# BioHackBoardPolulu.net
KiCad netlist of a schematic drawn in EAGLE
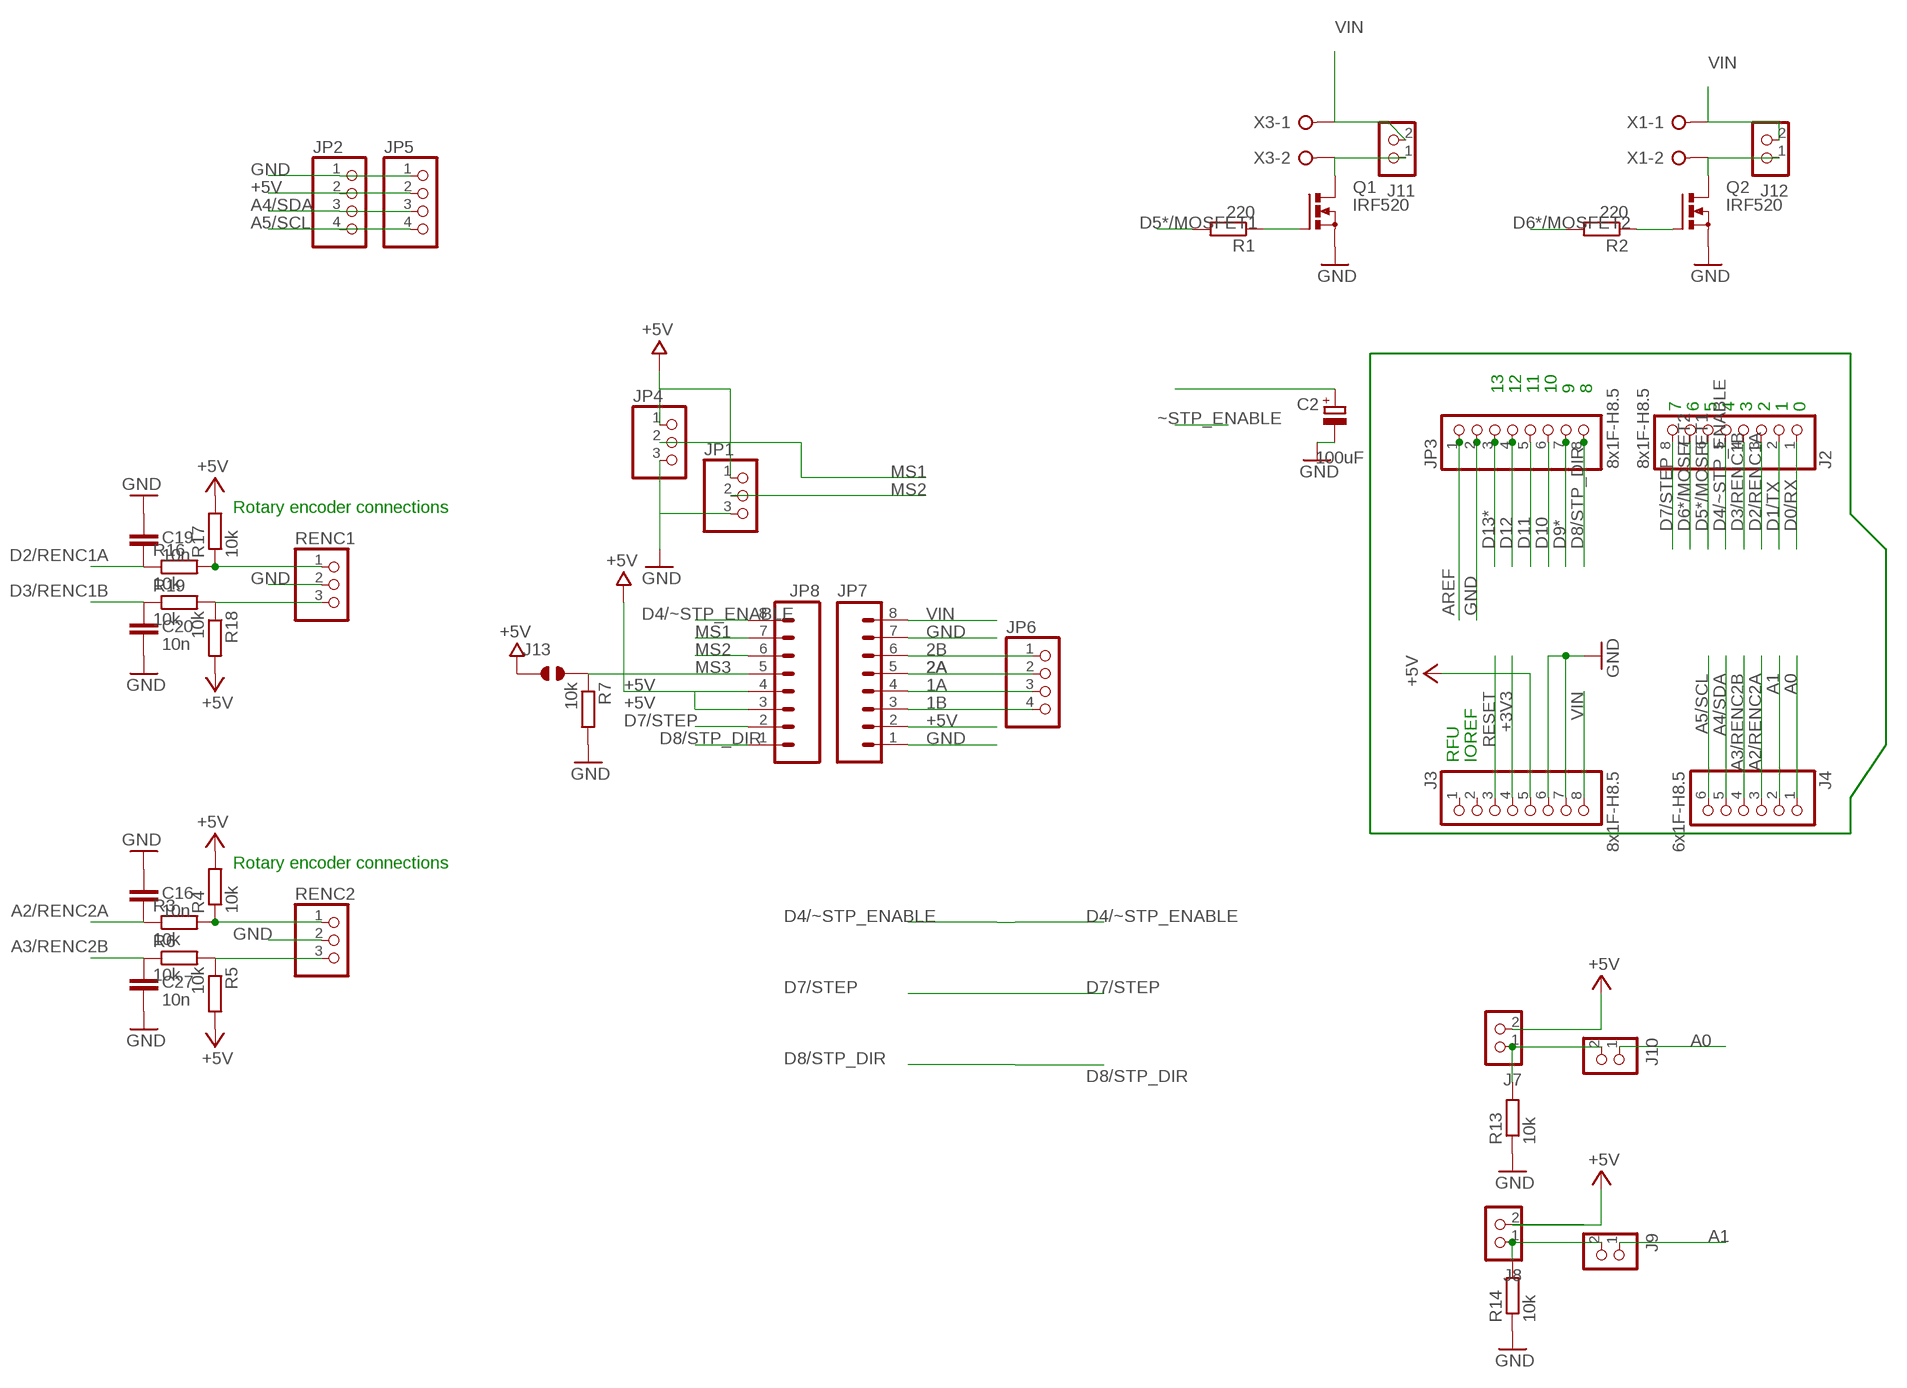
[diagram p0: schematic, sheet 1]

(export (version "E")
  (design (tool "Eeschema 10.0.6"))
  (components
    (comp (ref "C2")
      (value "100uF")
      (footprint "eagle-import:E2,5-7")
      (libsource (lib "eagle-import") (part "CPOL-EUE2.5-7"))
    )
    (comp (ref "C16")
      (value "10n")
      (footprint "eagle-import:C0603-ROUND")
      (libsource (lib "eagle-import") (part "C-EUC0603"))
    )
    (comp (ref "C19")
      (value "10n")
      (footprint "eagle-import:C0603-ROUND")
      (libsource (lib "eagle-import") (part "C-EUC0603"))
    )
    (comp (ref "C20")
      (value "10n")
      (footprint "eagle-import:C0603-ROUND")
      (libsource (lib "eagle-import") (part "C-EUC0603"))
    )
    (comp (ref "C27")
      (value "10n")
      (footprint "eagle-import:C0603-ROUND")
      (libsource (lib "eagle-import") (part "C-EUC0603"))
    )
    (comp (ref "J2")
      (value "8x1F-H8.5")
      (footprint "eagle-import:1X08-S")
      (libsource (lib "eagle-import") (part "PINHD-1X08_2.54-S"))
    )
    (comp (ref "J3")
      (value "8x1F-H8.5")
      (footprint "eagle-import:1X08-S")
      (libsource (lib "eagle-import") (part "PINHD-1X08_2.54-S"))
    )
    (comp (ref "J4")
      (value "6x1F-H8.5")
      (footprint "eagle-import:1X06-S")
      (libsource (lib "eagle-import") (part "PINHD-1X06_2.54-S"))
    )
    (comp (ref "J7")
      (value "CON_HEADER_1X02-PTH")
      (footprint "eagle-import:M1X2")
      (libsource (lib "eagle-import") (part "CON_HEADER_1X02-PTH"))
    )
    (comp (ref "J8")
      (value "CON_HEADER_1X02-PTH")
      (footprint "eagle-import:M1X2")
      (libsource (lib "eagle-import") (part "CON_HEADER_1X02-PTH"))
    )
    (comp (ref "J9")
      (value "CON_HEADER_1X02-PTH")
      (footprint "eagle-import:M1X2")
      (libsource (lib "eagle-import") (part "CON_HEADER_1X02-PTH"))
    )
    (comp (ref "J10")
      (value "CON_HEADER_1X02-PTH")
      (footprint "eagle-import:M1X2")
      (libsource (lib "eagle-import") (part "CON_HEADER_1X02-PTH"))
    )
    (comp (ref "J11")
      (value "CON_HEADER_1X02-PTH")
      (footprint "eagle-import:M1X2")
      (libsource (lib "eagle-import") (part "CON_HEADER_1X02-PTH"))
    )
    (comp (ref "J12")
      (value "CON_HEADER_1X02-PTH")
      (footprint "eagle-import:M1X2")
      (libsource (lib "eagle-import") (part "CON_HEADER_1X02-PTH"))
    )
    (comp (ref "J13")
      (value "JUMPER_SOLDER_1X2")
      (footprint "eagle-import:JUMPER_SOLDER_1X2")
      (libsource (lib "eagle-import") (part "JUMPER_SOLDER_1X2"))
    )
    (comp (ref "JP1")
      (value "PINHD-1X03_2.54-S")
      (footprint "eagle-import:1X03-S")
      (libsource (lib "eagle-import") (part "PINHD-1X03_2.54-S"))
    )
    (comp (ref "JP2")
      (value "PINHD-1X04_2.54-S")
      (footprint "eagle-import:1X04-S")
      (libsource (lib "eagle-import") (part "PINHD-1X04_2.54-S"))
    )
    (comp (ref "JP3")
      (value "8x1F-H8.5")
      (footprint "eagle-import:1X08-S")
      (libsource (lib "eagle-import") (part "PINHD-1X08_2.54-S"))
    )
    (comp (ref "JP4")
      (value "PINHD-1X03_2.54-S")
      (footprint "eagle-import:1X03-S")
      (libsource (lib "eagle-import") (part "PINHD-1X03_2.54-S"))
    )
    (comp (ref "JP5")
      (value "PINHD-1X04_2.54-S")
      (footprint "eagle-import:1X04-S")
      (libsource (lib "eagle-import") (part "PINHD-1X04_2.54-S"))
    )
    (comp (ref "JP6")
      (value "PINHD-1X04_2.54-S")
      (footprint "eagle-import:1X04-S")
      (libsource (lib "eagle-import") (part "PINHD-1X04_2.54-S"))
    )
    (comp (ref "JP7")
      (value "M081X08")
      (footprint "eagle-import:1X08")
      (libsource (lib "eagle-import") (part "M081X08"))
    )
    (comp (ref "JP8")
      (value "M081X08")
      (footprint "eagle-import:1X08")
      (libsource (lib "eagle-import") (part "M081X08"))
    )
    (comp (ref "Q1")
      (value "IRF520")
      (footprint "eagle-import:TO220BV")
      (libsource (lib "eagle-import") (part "IRF512"))
    )
    (comp (ref "Q2")
      (value "IRF520")
      (footprint "eagle-import:TO220BV")
      (libsource (lib "eagle-import") (part "IRF512"))
    )
    (comp (ref "R1")
      (value "220")
      (footprint "eagle-import:R0603-ROUND")
      (libsource (lib "eagle-import") (part "R-EU_R0603"))
    )
    (comp (ref "R2")
      (value "220")
      (footprint "eagle-import:R0603-ROUND")
      (libsource (lib "eagle-import") (part "R-EU_R0603"))
    )
    (comp (ref "R3")
      (value "10k")
      (footprint "eagle-import:R0603-ROUND")
      (libsource (lib "eagle-import") (part "R-EU_R0603"))
    )
    (comp (ref "R4")
      (value "10k")
      (footprint "eagle-import:R0603-ROUND")
      (libsource (lib "eagle-import") (part "R-EU_R0603"))
    )
    (comp (ref "R5")
      (value "10k")
      (footprint "eagle-import:R0603-ROUND")
      (libsource (lib "eagle-import") (part "R-EU_R0603"))
    )
    (comp (ref "R6")
      (value "10k")
      (footprint "eagle-import:R0603-ROUND")
      (libsource (lib "eagle-import") (part "R-EU_R0603"))
    )
    (comp (ref "R7")
      (value "10k")
      (footprint "eagle-import:R0603-ROUND")
      (libsource (lib "eagle-import") (part "R-EU_R0603"))
    )
    (comp (ref "R13")
      (value "10k")
      (footprint "eagle-import:R0603")
      (libsource (lib "eagle-import") (part "rcl_R-EU_R0603"))
    )
    (comp (ref "R14")
      (value "10k")
      (footprint "eagle-import:R0603")
      (libsource (lib "eagle-import") (part "rcl_R-EU_R0603"))
    )
    (comp (ref "R16")
      (value "10k")
      (footprint "eagle-import:R0603-ROUND")
      (libsource (lib "eagle-import") (part "R-EU_R0603"))
    )
    (comp (ref "R17")
      (value "10k")
      (footprint "eagle-import:R0603-ROUND")
      (libsource (lib "eagle-import") (part "R-EU_R0603"))
    )
    (comp (ref "R18")
      (value "10k")
      (footprint "eagle-import:R0603-ROUND")
      (libsource (lib "eagle-import") (part "R-EU_R0603"))
    )
    (comp (ref "R19")
      (value "10k")
      (footprint "eagle-import:R0603-ROUND")
      (libsource (lib "eagle-import") (part "R-EU_R0603"))
    )
    (comp (ref "RENC1")
      (value "PINHD-1X03_2.54-S")
      (footprint "eagle-import:1X03-S")
      (libsource (lib "eagle-import") (part "PINHD-1X03_2.54-S"))
    )
    (comp (ref "RENC2")
      (value "PINHD-1X03_2.54-S")
      (footprint "eagle-import:1X03-S")
      (libsource (lib "eagle-import") (part "PINHD-1X03_2.54-S"))
    )
    (comp (ref "X1")
      (value "W237-02P")
      (footprint "eagle-import:W237-132")
      (libsource (lib "eagle-import") (part "W237-02P"))
    )
    (comp (ref "X3")
      (value "W237-02P")
      (footprint "eagle-import:W237-132")
      (libsource (lib "eagle-import") (part "W237-02P"))
    )
  )
  (nets
    (net (code "1") (name "+5V") (class "Default")
      (node (ref "J13") (pin "1") (pinfunction "1_1") (pintype "passive"))
      (node (ref "J3") (pin "5") (pinfunction "5_5") (pintype "passive"))
      (node (ref "J7") (pin "2") (pinfunction "2_2") (pintype "passive"))
      (node (ref "J8") (pin "2") (pinfunction "2_2") (pintype "passive"))
      (node (ref "JP1") (pin "1") (pinfunction "1_1") (pintype "passive"))
      (node (ref "JP2") (pin "2") (pinfunction "2_2") (pintype "passive"))
      (node (ref "JP4") (pin "1") (pinfunction "1_1") (pintype "passive"))
      (node (ref "JP5") (pin "2") (pinfunction "2_2") (pintype "passive"))
      (node (ref "JP7") (pin "2") (pinfunction "2_2") (pintype "passive"))
      (node (ref "JP8") (pin "3") (pinfunction "3_3") (pintype "passive"))
      (node (ref "JP8") (pin "4") (pinfunction "4_4") (pintype "passive"))
      (node (ref "R17") (pin "2") (pinfunction "2_2") (pintype "passive"))
      (node (ref "R18") (pin "2") (pinfunction "2_2") (pintype "passive"))
      (node (ref "R4") (pin "2") (pinfunction "2_2") (pintype "passive"))
      (node (ref "R5") (pin "2") (pinfunction "2_2") (pintype "passive"))
    )
    (net (code "2") (name "/+3V3") (class "Default")
      (node (ref "J3") (pin "4") (pinfunction "4_4") (pintype "passive"))
    )
    (net (code "3") (name "/1A") (class "Default")
      (node (ref "JP6") (pin "3") (pinfunction "3_3") (pintype "passive"))
      (node (ref "JP7") (pin "4") (pinfunction "4_4") (pintype "passive"))
    )
    (net (code "4") (name "/1B") (class "Default")
      (node (ref "JP6") (pin "4") (pinfunction "4_4") (pintype "passive"))
      (node (ref "JP7") (pin "3") (pinfunction "3_3") (pintype "passive"))
    )
    (net (code "5") (name "/2A") (class "Default")
      (node (ref "JP6") (pin "2") (pinfunction "2_2") (pintype "passive"))
      (node (ref "JP7") (pin "5") (pinfunction "5_5") (pintype "passive"))
    )
    (net (code "6") (name "/2B") (class "Default")
      (node (ref "JP6") (pin "1") (pinfunction "1_1") (pintype "passive"))
      (node (ref "JP7") (pin "6") (pinfunction "6_6") (pintype "passive"))
    )
    (net (code "7") (name "/A0") (class "Default")
      (node (ref "J10") (pin "1") (pinfunction "1_1") (pintype "passive"))
      (node (ref "J4") (pin "1") (pinfunction "1_1") (pintype "passive"))
    )
    (net (code "8") (name "/A1") (class "Default")
      (node (ref "J4") (pin "2") (pinfunction "2_2") (pintype "passive"))
      (node (ref "J9") (pin "1") (pinfunction "1_1") (pintype "passive"))
    )
    (net (code "9") (name "/A2{slash}RENC2A") (class "Default")
      (node (ref "C16") (pin "1") (pinfunction "1_1") (pintype "passive"))
      (node (ref "J4") (pin "3") (pinfunction "3_3") (pintype "passive"))
      (node (ref "R3") (pin "1") (pinfunction "1_1") (pintype "passive"))
    )
    (net (code "10") (name "/A3{slash}RENC2B") (class "Default")
      (node (ref "C27") (pin "2") (pinfunction "2_2") (pintype "passive"))
      (node (ref "J4") (pin "4") (pinfunction "4_4") (pintype "passive"))
      (node (ref "R6") (pin "1") (pinfunction "1_1") (pintype "passive"))
    )
    (net (code "11") (name "/A4{slash}SDA") (class "Default")
      (node (ref "J4") (pin "5") (pinfunction "5_5") (pintype "passive"))
      (node (ref "JP2") (pin "3") (pinfunction "3_3") (pintype "passive"))
      (node (ref "JP5") (pin "3") (pinfunction "3_3") (pintype "passive"))
    )
    (net (code "12") (name "/A5{slash}SCL") (class "Default")
      (node (ref "J4") (pin "6") (pinfunction "6_6") (pintype "passive"))
      (node (ref "JP2") (pin "4") (pinfunction "4_4") (pintype "passive"))
      (node (ref "JP5") (pin "4") (pinfunction "4_4") (pintype "passive"))
    )
    (net (code "13") (name "/AREF") (class "Default")
      (node (ref "JP3") (pin "1") (pinfunction "1_1") (pintype "passive"))
    )
    (net (code "14") (name "/D0{slash}RX") (class "Default")
      (node (ref "J2") (pin "1") (pinfunction "1_1") (pintype "passive"))
    )
    (net (code "15") (name "/D1{slash}TX") (class "Default")
      (node (ref "J2") (pin "2") (pinfunction "2_2") (pintype "passive"))
    )
    (net (code "16") (name "/D2{slash}RENC1A") (class "Default")
      (node (ref "C19") (pin "1") (pinfunction "1_1") (pintype "passive"))
      (node (ref "J2") (pin "3") (pinfunction "3_3") (pintype "passive"))
      (node (ref "R16") (pin "1") (pinfunction "1_1") (pintype "passive"))
    )
    (net (code "17") (name "/D3{slash}RENC1B") (class "Default")
      (node (ref "C20") (pin "2") (pinfunction "2_2") (pintype "passive"))
      (node (ref "J2") (pin "4") (pinfunction "4_4") (pintype "passive"))
      (node (ref "R19") (pin "1") (pinfunction "1_1") (pintype "passive"))
    )
    (net (code "18") (name "/D4{slash}~{STP_ENABLE}") (class "Default")
      (node (ref "J2") (pin "5") (pinfunction "5_5") (pintype "passive"))
      (node (ref "JP8") (pin "8") (pinfunction "8_8") (pintype "passive"))
    )
    (net (code "19") (name "/D5*{slash}MOSFET1") (class "Default")
      (node (ref "J2") (pin "6") (pinfunction "6_6") (pintype "passive"))
      (node (ref "R1") (pin "2") (pinfunction "2_2") (pintype "passive"))
    )
    (net (code "20") (name "/D6*{slash}MOSFET2") (class "Default")
      (node (ref "J2") (pin "7") (pinfunction "7_7") (pintype "passive"))
      (node (ref "R2") (pin "2") (pinfunction "2_2") (pintype "passive"))
    )
    (net (code "21") (name "/D7{slash}STEP") (class "Default")
      (node (ref "J2") (pin "8") (pinfunction "8_8") (pintype "passive"))
      (node (ref "JP8") (pin "2") (pinfunction "2_2") (pintype "passive"))
    )
    (net (code "22") (name "/D8{slash}STP_DIR") (class "Default")
      (node (ref "JP3") (pin "8") (pinfunction "8_8") (pintype "passive"))
      (node (ref "JP8") (pin "1") (pinfunction "1_1") (pintype "passive"))
    )
    (net (code "23") (name "/D9*") (class "Default")
      (node (ref "JP3") (pin "7") (pinfunction "7_7") (pintype "passive"))
    )
    (net (code "24") (name "/D10") (class "Default")
      (node (ref "JP3") (pin "6") (pinfunction "6_6") (pintype "passive"))
    )
    (net (code "25") (name "/D11") (class "Default")
      (node (ref "JP3") (pin "5") (pinfunction "5_5") (pintype "passive"))
    )
    (net (code "26") (name "/D12") (class "Default")
      (node (ref "JP3") (pin "4") (pinfunction "4_4") (pintype "passive"))
    )
    (net (code "27") (name "/D13*") (class "Default")
      (node (ref "JP3") (pin "3") (pinfunction "3_3") (pintype "passive"))
    )
    (net (code "28") (name "/MS1") (class "Default")
      (node (ref "JP4") (pin "2") (pinfunction "2_2") (pintype "passive"))
      (node (ref "JP8") (pin "7") (pinfunction "7_7") (pintype "passive"))
    )
    (net (code "29") (name "/MS2") (class "Default")
      (node (ref "JP1") (pin "2") (pinfunction "2_2") (pintype "passive"))
      (node (ref "JP8") (pin "6") (pinfunction "6_6") (pintype "passive"))
    )
    (net (code "30") (name "/MS3") (class "Default")
      (node (ref "J13") (pin "2") (pinfunction "2_2") (pintype "passive"))
      (node (ref "JP8") (pin "5") (pinfunction "5_5") (pintype "passive"))
      (node (ref "R7") (pin "1") (pinfunction "1_1") (pintype "passive"))
    )
    (net (code "31") (name "/RESET") (class "Default")
      (node (ref "J3") (pin "3") (pinfunction "3_3") (pintype "passive"))
    )
    (net (code "32") (name "/VIN") (class "Default")
      (node (ref "C2") (pin "+") (pinfunction "+_+") (pintype "passive"))
      (node (ref "J11") (pin "2") (pinfunction "2_2") (pintype "passive"))
      (node (ref "J12") (pin "2") (pinfunction "2_2") (pintype "passive"))
      (node (ref "J3") (pin "8") (pinfunction "8_8") (pintype "passive"))
      (node (ref "JP7") (pin "8") (pinfunction "8_8") (pintype "passive"))
      (node (ref "X1") (pin "1") (pinfunction "KL_1") (pintype "passive"))
      (node (ref "X3") (pin "1") (pinfunction "KL_1") (pintype "passive"))
    )
    (net (code "34") (name "GND") (class "Default")
      (node (ref "C16") (pin "2") (pinfunction "2_2") (pintype "passive"))
      (node (ref "C19") (pin "2") (pinfunction "2_2") (pintype "passive"))
      (node (ref "C2") (pin "-") (pinfunction "-_-") (pintype "passive"))
      (node (ref "C20") (pin "1") (pinfunction "1_1") (pintype "passive"))
      (node (ref "C27") (pin "1") (pinfunction "1_1") (pintype "passive"))
      (node (ref "J3") (pin "6") (pinfunction "6_6") (pintype "passive"))
      (node (ref "J3") (pin "7") (pinfunction "7_7") (pintype "passive"))
      (node (ref "JP1") (pin "3") (pinfunction "3_3") (pintype "passive"))
      (node (ref "JP2") (pin "1") (pinfunction "1_1") (pintype "passive"))
      (node (ref "JP3") (pin "2") (pinfunction "2_2") (pintype "passive"))
      (node (ref "JP4") (pin "3") (pinfunction "3_3") (pintype "passive"))
      (node (ref "JP5") (pin "1") (pinfunction "1_1") (pintype "passive"))
      (node (ref "JP7") (pin "1") (pinfunction "1_1") (pintype "passive"))
      (node (ref "JP7") (pin "7") (pinfunction "7_7") (pintype "passive"))
      (node (ref "Q1") (pin "S") (pinfunction "S_S") (pintype "passive"))
      (node (ref "Q2") (pin "S") (pinfunction "S_S") (pintype "passive"))
      (node (ref "R13") (pin "1") (pinfunction "1_1") (pintype "passive"))
      (node (ref "R14") (pin "1") (pinfunction "1_1") (pintype "passive"))
      (node (ref "R7") (pin "2") (pinfunction "2_2") (pintype "passive"))
      (node (ref "RENC1") (pin "2") (pinfunction "2_2") (pintype "passive"))
      (node (ref "RENC2") (pin "2") (pinfunction "2_2") (pintype "passive"))
    )
    (net (code "35") (name "Net-(J8-Pad1)") (class "Default")
      (node (ref "J8") (pin "1") (pinfunction "1_1") (pintype "passive"))
      (node (ref "J9") (pin "2") (pinfunction "2_2") (pintype "passive"))
      (node (ref "R14") (pin "2") (pinfunction "2_2") (pintype "passive"))
    )
    (net (code "36") (name "Net-(J10-Pad2)") (class "Default")
      (node (ref "J10") (pin "2") (pinfunction "2_2") (pintype "passive"))
      (node (ref "J7") (pin "1") (pinfunction "1_1") (pintype "passive"))
      (node (ref "R13") (pin "2") (pinfunction "2_2") (pintype "passive"))
    )
    (net (code "37") (name "Net-(Q1-PadG)") (class "Default")
      (node (ref "Q1") (pin "G") (pinfunction "G_G") (pintype "passive"))
      (node (ref "R1") (pin "1") (pinfunction "1_1") (pintype "passive"))
    )
    (net (code "38") (name "Net-(Q2-PadG)") (class "Default")
      (node (ref "Q2") (pin "G") (pinfunction "G_G") (pintype "passive"))
      (node (ref "R2") (pin "1") (pinfunction "1_1") (pintype "passive"))
    )
    (net (code "39") (name "Net-(R3-Pad2)") (class "Default")
      (node (ref "R3") (pin "2") (pinfunction "2_2") (pintype "passive"))
      (node (ref "R4") (pin "1") (pinfunction "1_1") (pintype "passive"))
      (node (ref "RENC2") (pin "1") (pinfunction "1_1") (pintype "passive"))
    )
    (net (code "40") (name "Net-(R5-Pad1)") (class "Default")
      (node (ref "R5") (pin "1") (pinfunction "1_1") (pintype "passive"))
      (node (ref "R6") (pin "2") (pinfunction "2_2") (pintype "passive"))
      (node (ref "RENC2") (pin "3") (pinfunction "3_3") (pintype "passive"))
    )
    (net (code "41") (name "Net-(R16-Pad2)") (class "Default")
      (node (ref "R16") (pin "2") (pinfunction "2_2") (pintype "passive"))
      (node (ref "R17") (pin "1") (pinfunction "1_1") (pintype "passive"))
      (node (ref "RENC1") (pin "1") (pinfunction "1_1") (pintype "passive"))
    )
    (net (code "42") (name "Net-(R18-Pad1)") (class "Default")
      (node (ref "R18") (pin "1") (pinfunction "1_1") (pintype "passive"))
      (node (ref "R19") (pin "2") (pinfunction "2_2") (pintype "passive"))
      (node (ref "RENC1") (pin "3") (pinfunction "3_3") (pintype "passive"))
    )
    (net (code "43") (name "Net-(X1B-KL)") (class "Default")
      (node (ref "J12") (pin "1") (pinfunction "1_1") (pintype "passive"))
      (node (ref "Q2") (pin "D") (pinfunction "D_D") (pintype "passive"))
      (node (ref "X1") (pin "2") (pinfunction "KL_2") (pintype "passive"))
    )
    (net (code "44") (name "Net-(X3B-KL)") (class "Default")
      (node (ref "J11") (pin "1") (pinfunction "1_1") (pintype "passive"))
      (node (ref "Q1") (pin "D") (pinfunction "D_D") (pintype "passive"))
      (node (ref "X3") (pin "2") (pinfunction "KL_2") (pintype "passive"))
    )
    (net (code "45") (name "unconnected-(J3-Pad1)") (class "Default")
      (node (ref "J3") (pin "1") (pinfunction "1_1") (pintype "passive"))
    )
    (net (code "46") (name "unconnected-(J3-Pad2)") (class "Default")
      (node (ref "J3") (pin "2") (pinfunction "2_2") (pintype "passive"))
    )
  )
)
